# ETH_CON.net
KiCad netlist of a schematic drawn in Altium Designer
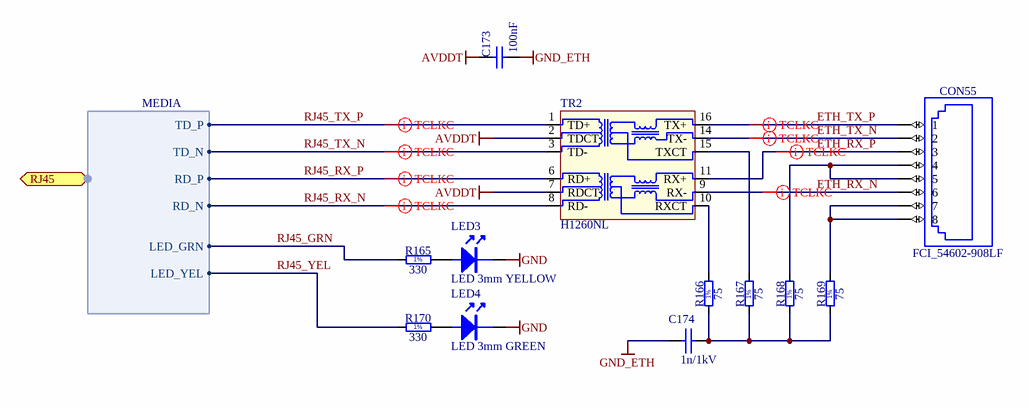
[diagram p0: ETH_CON.SchDoc]

(export (version "E")
  (design (tool "Eeschema 10.0.6"))
  (components
    (comp (ref "C173")
      (value "100nF")
      (footprint "CAPC1005X55N")
      (description "Non-polarised capacitor")
      (fields
        (field (name "PART NUMBER") "CC0402_100NF_16V_10%_X7R")
        (field (name "VOLTAGE") "16V")
        (field (name "AUTHOR") "CERN DEM JLC")
      )
      (libsource (lib "Capacitors") (part "Capacitor - non polarized"))
    )
    (comp (ref "C174")
      (value "1n/1kV")
      (footprint "cap_ceram")
      (description "Capacitor")
      (libsource (lib "LIBRARY_SCH") (part "CAP"))
    )
    (comp (ref "CON55")
      (value "FCI_54602-908LF")
      (footprint "FCI_54602-908LF")
      (description "1 Port, 8 Positions, CAT3 RJ45 Horizontal Modular Jack")
      (fields
        (field (name "MANUFACTURER") "FCI")
        (field (name "MANUFACTURER PART NUMBER") "54602-908LF")
        (field (name "AUTHOR") "CERN DEM JLC")
      )
      (libsource (lib "Connectors") (part "FCI_54602-908LF"))
    )
    (comp (ref "LED3")
      (value "LED 3mm YELLOW")
      (footprint "LED")
      (description "LED")
      (libsource (lib "LIBRARY_SCH") (part "LED"))
    )
    (comp (ref "LED4")
      (value "LED 3mm GREEN")
      (footprint "LED")
      (description "LED")
      (libsource (lib "LIBRARY_SCH") (part "LED"))
    )
    (comp (ref "R165")
      (value "330")
      (footprint "RESC1608X55N")
      (description "Resistor - 1%")
      (fields
        (field (name "PART NUMBER") "R0603_330R_1%_0.1W_100PPM")
        (field (name "POWER") "0.1W")
        (field (name "AUTHOR") "CERN DEM JLC")
      )
      (libsource (lib "Resistors") (part "Resistor - 1%"))
    )
    (comp (ref "R166")
      (value "75")
      (footprint "RESC1608X55N")
      (description "Resistor - 1%")
      (fields
        (field (name "PART NUMBER") "R0603_75R_1%_0.1W_100PPM")
        (field (name "POWER") "0.1W")
        (field (name "AUTHOR") "CERN DEM JLC")
      )
      (libsource (lib "Resistors") (part "Resistor - 1%"))
    )
    (comp (ref "R167")
      (value "75")
      (footprint "RESC1608X55N")
      (description "Resistor - 1%")
      (fields
        (field (name "PART NUMBER") "R0603_75R_1%_0.1W_100PPM")
        (field (name "POWER") "0.1W")
        (field (name "AUTHOR") "CERN DEM JLC")
      )
      (libsource (lib "Resistors") (part "Resistor - 1%"))
    )
    (comp (ref "R168")
      (value "75")
      (footprint "RESC1608X55N")
      (description "Resistor - 1%")
      (fields
        (field (name "PART NUMBER") "R0603_75R_1%_0.1W_100PPM")
        (field (name "POWER") "0.1W")
        (field (name "AUTHOR") "CERN DEM JLC")
      )
      (libsource (lib "Resistors") (part "Resistor - 1%"))
    )
    (comp (ref "R169")
      (value "75")
      (footprint "RESC1608X55N")
      (description "Resistor - 1%")
      (fields
        (field (name "PART NUMBER") "R0603_75R_1%_0.1W_100PPM")
        (field (name "POWER") "0.1W")
        (field (name "AUTHOR") "CERN DEM JLC")
      )
      (libsource (lib "Resistors") (part "Resistor - 1%"))
    )
    (comp (ref "R170")
      (value "330")
      (footprint "RESC1608X55N")
      (description "Resistor - 1%")
      (fields
        (field (name "PART NUMBER") "R0603_330R_1%_0.1W_100PPM")
        (field (name "POWER") "0.1W")
        (field (name "AUTHOR") "CERN DEM JLC")
      )
      (libsource (lib "Resistors") (part "Resistor - 1%"))
    )
    (comp (ref "TR2")
      (value "H1260NL")
      (footprint "H1260NL")
      (description "ethernet trafo (TME)")
      (libsource (lib "*") (part "TR_H1260NL"))
    )
  )
  (nets
    (net (code "2") (name "/ETH_RX_N") (class "Default")
      (node (ref "CON55") (pin "6") (pinfunction "6_6") (pintype "bidirectional"))
      (node (ref "TR2") (pin "9") (pinfunction "RX-_9") (pintype "power_in"))
    )
    (net (code "3") (name "/ETH_RX_P") (class "Default")
      (node (ref "CON55") (pin "3") (pinfunction "3_3") (pintype "bidirectional"))
      (node (ref "TR2") (pin "11") (pinfunction "RX+_11") (pintype "power_in"))
    )
    (net (code "4") (name "/ETH_TX_N") (class "Default")
      (node (ref "CON55") (pin "2") (pinfunction "2_2") (pintype "bidirectional"))
      (node (ref "TR2") (pin "14") (pinfunction "TX-_14") (pintype "power_in"))
    )
    (net (code "5") (name "/ETH_TX_P") (class "Default")
      (node (ref "CON55") (pin "1") (pinfunction "1_1") (pintype "bidirectional"))
      (node (ref "TR2") (pin "16") (pinfunction "TX+_16") (pintype "power_in"))
    )
    (net (code "6") (name "/RJ45_GRN") (class "Default")
      (node (ref "R165") (pin "1") (pinfunction "1_1") (pintype "passive"))
    )
    (net (code "7") (name "/RJ45_RX_N") (class "Default")
      (node (ref "TR2") (pin "8") (pinfunction "RD-_8") (pintype "passive"))
    )
    (net (code "8") (name "/RJ45_RX_P") (class "Default")
      (node (ref "TR2") (pin "6") (pinfunction "RD+_6") (pintype "passive"))
    )
    (net (code "9") (name "/RJ45_TX_N") (class "Default")
      (node (ref "TR2") (pin "3") (pinfunction "TD-_3") (pintype "passive"))
    )
    (net (code "10") (name "/RJ45_TX_P") (class "Default")
      (node (ref "TR2") (pin "1") (pinfunction "TD+_1") (pintype "passive"))
    )
    (net (code "11") (name "/RJ45_YEL") (class "Default")
      (node (ref "R170") (pin "1") (pinfunction "1_1") (pintype "passive"))
    )
    (net (code "13") (name "AVDDT") (class "Default")
      (node (ref "C173") (pin "2") (pinfunction "2_2") (pintype "passive"))
      (node (ref "TR2") (pin "2") (pinfunction "TDCT_2") (pintype "passive"))
      (node (ref "TR2") (pin "7") (pinfunction "RDCT_7") (pintype "passive"))
    )
    (net (code "14") (name "GND") (class "Default")
      (node (ref "LED3") (pin "K") (pinfunction "K_K") (pintype "passive"))
      (node (ref "LED4") (pin "K") (pinfunction "K_K") (pintype "passive"))
    )
    (net (code "15") (name "GND_ETH") (class "Default")
      (node (ref "C173") (pin "1") (pinfunction "1_1") (pintype "passive"))
      (node (ref "C174") (pin "1") (pinfunction "1_1") (pintype "passive"))
    )
    (net (code "16") (name "Net-(C174-Pad2)") (class "Default")
      (node (ref "C174") (pin "2") (pinfunction "2_2") (pintype "passive"))
      (node (ref "R166") (pin "1") (pinfunction "1_1") (pintype "passive"))
      (node (ref "R167") (pin "1") (pinfunction "1_1") (pintype "passive"))
      (node (ref "R168") (pin "1") (pinfunction "1_1") (pintype "passive"))
      (node (ref "R169") (pin "1") (pinfunction "1_1") (pintype "passive"))
    )
    (net (code "17") (name "Net-(CON55-Pad4)") (class "Default")
      (node (ref "CON55") (pin "4") (pinfunction "4_4") (pintype "bidirectional"))
      (node (ref "CON55") (pin "5") (pinfunction "5_5") (pintype "bidirectional"))
      (node (ref "R168") (pin "2") (pinfunction "2_2") (pintype "passive"))
    )
    (net (code "18") (name "Net-(CON55-Pad7)") (class "Default")
      (node (ref "CON55") (pin "7") (pinfunction "7_7") (pintype "bidirectional"))
      (node (ref "CON55") (pin "8") (pinfunction "8_8") (pintype "bidirectional"))
      (node (ref "R169") (pin "2") (pinfunction "2_2") (pintype "passive"))
    )
    (net (code "19") (name "Net-(LED3-PadA)") (class "Default")
      (node (ref "LED3") (pin "A") (pinfunction "A_A") (pintype "passive"))
      (node (ref "R165") (pin "2") (pinfunction "2_2") (pintype "passive"))
    )
    (net (code "20") (name "Net-(LED4-PadA)") (class "Default")
      (node (ref "LED4") (pin "A") (pinfunction "A_A") (pintype "passive"))
      (node (ref "R170") (pin "2") (pinfunction "2_2") (pintype "passive"))
    )
    (net (code "21") (name "Net-(TR2-RXCT)") (class "Default")
      (node (ref "R166") (pin "2") (pinfunction "2_2") (pintype "passive"))
      (node (ref "TR2") (pin "10") (pinfunction "RXCT_10") (pintype "power_in"))
    )
    (net (code "22") (name "Net-(TR2-TXCT)") (class "Default")
      (node (ref "R167") (pin "2") (pinfunction "2_2") (pintype "passive"))
      (node (ref "TR2") (pin "15") (pinfunction "TXCT_15") (pintype "power_in"))
    )
  )
)
